# protoboard.net
KiCad netlist of a schematic drawn in EAGLE
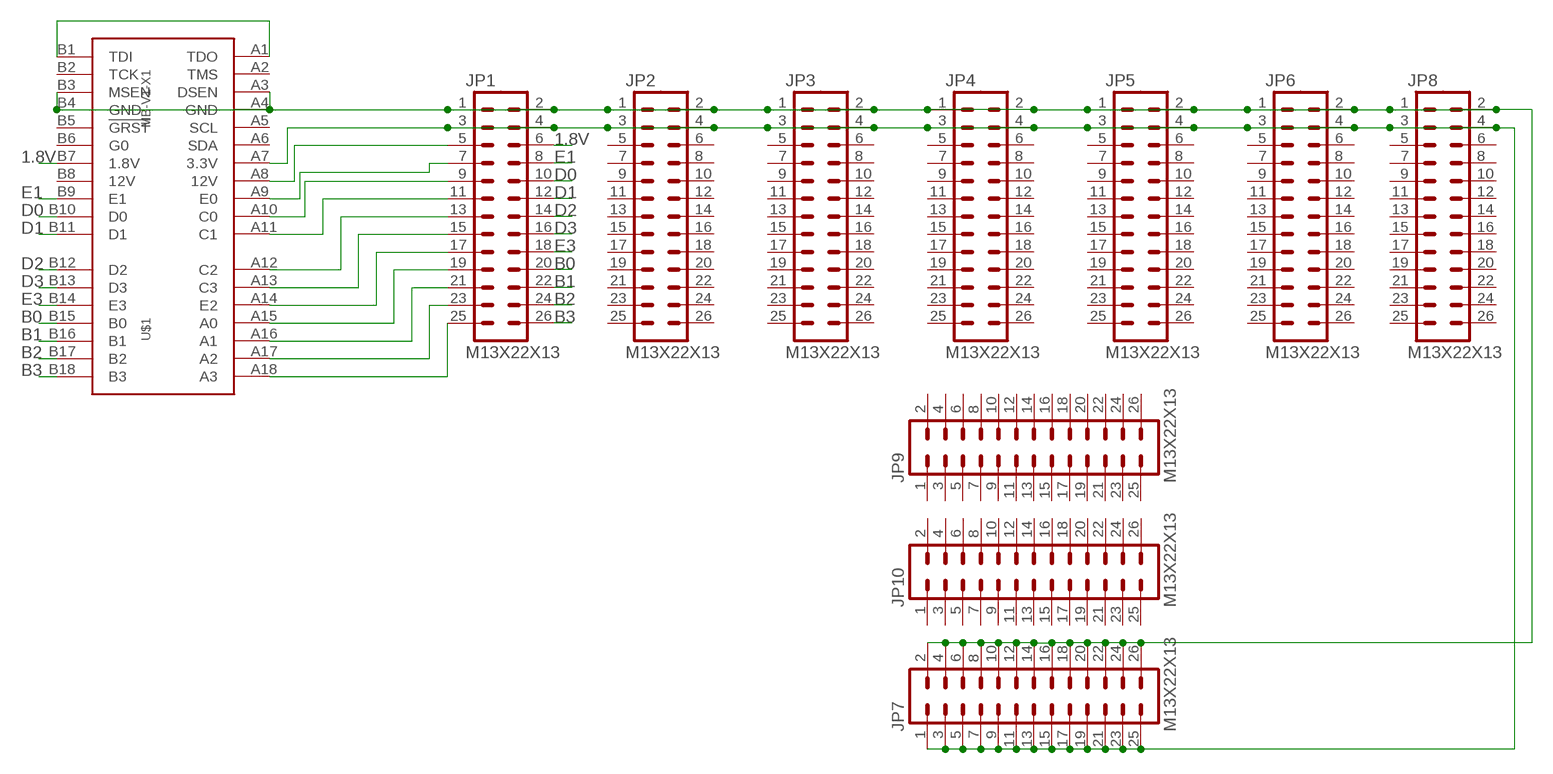
[diagram p0: schematic, sheet 1]

(export (version "E")
  (design (tool "Eeschema 10.0.6"))
  (components
    (comp (ref "JP1")
      (value "M13X22X13")
      (footprint "eagle-import:2X13")
      (libsource (lib "eagle-import") (part "M13X22X13"))
    )
    (comp (ref "JP2")
      (value "M13X22X13")
      (footprint "eagle-import:2X13")
      (libsource (lib "eagle-import") (part "M13X22X13"))
    )
    (comp (ref "JP3")
      (value "M13X22X13")
      (footprint "eagle-import:2X13")
      (libsource (lib "eagle-import") (part "M13X22X13"))
    )
    (comp (ref "JP4")
      (value "M13X22X13")
      (footprint "eagle-import:2X13")
      (libsource (lib "eagle-import") (part "M13X22X13"))
    )
    (comp (ref "JP5")
      (value "M13X22X13")
      (footprint "eagle-import:2X13")
      (libsource (lib "eagle-import") (part "M13X22X13"))
    )
    (comp (ref "JP6")
      (value "M13X22X13")
      (footprint "eagle-import:2X13")
      (libsource (lib "eagle-import") (part "M13X22X13"))
    )
    (comp (ref "JP7")
      (value "M13X22X13")
      (footprint "eagle-import:2X13")
      (libsource (lib "eagle-import") (part "M13X22X13"))
    )
    (comp (ref "JP8")
      (value "M13X22X13")
      (footprint "eagle-import:2X13")
      (libsource (lib "eagle-import") (part "M13X22X13"))
    )
    (comp (ref "JP9")
      (value "M13X22X13")
      (footprint "eagle-import:2X13")
      (libsource (lib "eagle-import") (part "M13X22X13"))
    )
    (comp (ref "JP10")
      (value "M13X22X13")
      (footprint "eagle-import:2X13")
      (libsource (lib "eagle-import") (part "M13X22X13"))
    )
    (comp (ref "U$1")
      (value "MB-V1-X1")
      (footprint "eagle-import:PCIE-X1-EDGE")
      (libsource (lib "eagle-import") (part "MB-V1-X1"))
    )
  )
  (nets
    (net (code "1") (name "/1.8V") (class "Default")
      (node (ref "JP1") (pin "6") (pinfunction "6_6") (pintype "passive"))
      (node (ref "U$1") (pin "B7") (pinfunction "1.8V_B7") (pintype "bidirectional"))
    )
    (net (code "2") (name "/B0") (class "Default")
      (node (ref "JP1") (pin "20") (pinfunction "20_20") (pintype "passive"))
      (node (ref "U$1") (pin "B15") (pinfunction "B0_B15") (pintype "bidirectional"))
    )
    (net (code "3") (name "/B1") (class "Default")
      (node (ref "JP1") (pin "22") (pinfunction "22_22") (pintype "passive"))
      (node (ref "U$1") (pin "B16") (pinfunction "B1_B16") (pintype "bidirectional"))
    )
    (net (code "4") (name "/B2") (class "Default")
      (node (ref "JP1") (pin "24") (pinfunction "24_24") (pintype "passive"))
      (node (ref "U$1") (pin "B17") (pinfunction "B2_B17") (pintype "bidirectional"))
    )
    (net (code "5") (name "/B3") (class "Default")
      (node (ref "JP1") (pin "26") (pinfunction "26_26") (pintype "passive"))
      (node (ref "U$1") (pin "B18") (pinfunction "B3_B18") (pintype "bidirectional"))
    )
    (net (code "6") (name "/D0") (class "Default")
      (node (ref "JP1") (pin "10") (pinfunction "10_10") (pintype "passive"))
      (node (ref "U$1") (pin "B10") (pinfunction "D0_B10") (pintype "bidirectional"))
    )
    (net (code "7") (name "/D1") (class "Default")
      (node (ref "JP1") (pin "12") (pinfunction "12_12") (pintype "passive"))
      (node (ref "U$1") (pin "B11") (pinfunction "D1_B11") (pintype "bidirectional"))
    )
    (net (code "8") (name "/D2") (class "Default")
      (node (ref "JP1") (pin "14") (pinfunction "14_14") (pintype "passive"))
      (node (ref "U$1") (pin "B12") (pinfunction "D2_B12") (pintype "bidirectional"))
    )
    (net (code "9") (name "/D3") (class "Default")
      (node (ref "JP1") (pin "16") (pinfunction "16_16") (pintype "passive"))
      (node (ref "U$1") (pin "B13") (pinfunction "D3_B13") (pintype "bidirectional"))
    )
    (net (code "10") (name "/E1") (class "Default")
      (node (ref "JP1") (pin "8") (pinfunction "8_8") (pintype "passive"))
      (node (ref "U$1") (pin "B9") (pinfunction "E1_B9") (pintype "bidirectional"))
    )
    (net (code "11") (name "/E3") (class "Default")
      (node (ref "JP1") (pin "18") (pinfunction "18_18") (pintype "passive"))
      (node (ref "U$1") (pin "B14") (pinfunction "E3_B14") (pintype "bidirectional"))
    )
    (net (code "12") (name "Net-(JP1-Pad5)") (class "Default")
      (node (ref "JP1") (pin "5") (pinfunction "5_5") (pintype "passive"))
      (node (ref "U$1") (pin "A8") (pinfunction "12V_A8") (pintype "bidirectional"))
    )
    (net (code "13") (name "Net-(U$1-3.3V)") (class "Default")
      (node (ref "JP1") (pin "3") (pinfunction "3_3") (pintype "passive"))
      (node (ref "JP1") (pin "4") (pinfunction "4_4") (pintype "passive"))
      (node (ref "JP2") (pin "3") (pinfunction "3_3") (pintype "passive"))
      (node (ref "JP2") (pin "4") (pinfunction "4_4") (pintype "passive"))
      (node (ref "JP3") (pin "3") (pinfunction "3_3") (pintype "passive"))
      (node (ref "JP3") (pin "4") (pinfunction "4_4") (pintype "passive"))
      (node (ref "JP4") (pin "3") (pinfunction "3_3") (pintype "passive"))
      (node (ref "JP4") (pin "4") (pinfunction "4_4") (pintype "passive"))
      (node (ref "JP5") (pin "3") (pinfunction "3_3") (pintype "passive"))
      (node (ref "JP5") (pin "4") (pinfunction "4_4") (pintype "passive"))
      (node (ref "JP6") (pin "3") (pinfunction "3_3") (pintype "passive"))
      (node (ref "JP6") (pin "4") (pinfunction "4_4") (pintype "passive"))
      (node (ref "JP7") (pin "1") (pinfunction "1_1") (pintype "passive"))
      (node (ref "JP7") (pin "11") (pinfunction "11_11") (pintype "passive"))
      (node (ref "JP7") (pin "13") (pinfunction "13_13") (pintype "passive"))
      (node (ref "JP7") (pin "15") (pinfunction "15_15") (pintype "passive"))
      (node (ref "JP7") (pin "17") (pinfunction "17_17") (pintype "passive"))
      (node (ref "JP7") (pin "19") (pinfunction "19_19") (pintype "passive"))
      (node (ref "JP7") (pin "21") (pinfunction "21_21") (pintype "passive"))
      (node (ref "JP7") (pin "23") (pinfunction "23_23") (pintype "passive"))
      (node (ref "JP7") (pin "25") (pinfunction "25_25") (pintype "passive"))
      (node (ref "JP7") (pin "3") (pinfunction "3_3") (pintype "passive"))
      (node (ref "JP7") (pin "5") (pinfunction "5_5") (pintype "passive"))
      (node (ref "JP7") (pin "7") (pinfunction "7_7") (pintype "passive"))
      (node (ref "JP7") (pin "9") (pinfunction "9_9") (pintype "passive"))
      (node (ref "JP8") (pin "3") (pinfunction "3_3") (pintype "passive"))
      (node (ref "JP8") (pin "4") (pinfunction "4_4") (pintype "passive"))
      (node (ref "U$1") (pin "A7") (pinfunction "3.3V_A7") (pintype "bidirectional"))
    )
    (net (code "14") (name "Net-(U$1-A0)") (class "Default")
      (node (ref "JP1") (pin "19") (pinfunction "19_19") (pintype "passive"))
      (node (ref "U$1") (pin "A15") (pinfunction "A0_A15") (pintype "bidirectional"))
    )
    (net (code "15") (name "Net-(U$1-A1)") (class "Default")
      (node (ref "JP1") (pin "21") (pinfunction "21_21") (pintype "passive"))
      (node (ref "U$1") (pin "A16") (pinfunction "A1_A16") (pintype "bidirectional"))
    )
    (net (code "16") (name "Net-(U$1-A2)") (class "Default")
      (node (ref "JP1") (pin "23") (pinfunction "23_23") (pintype "passive"))
      (node (ref "U$1") (pin "A17") (pinfunction "A2_A17") (pintype "bidirectional"))
    )
    (net (code "17") (name "Net-(U$1-A3)") (class "Default")
      (node (ref "JP1") (pin "25") (pinfunction "25_25") (pintype "passive"))
      (node (ref "U$1") (pin "A18") (pinfunction "A3_A18") (pintype "bidirectional"))
    )
    (net (code "18") (name "Net-(U$1-C0)") (class "Default")
      (node (ref "JP1") (pin "9") (pinfunction "9_9") (pintype "passive"))
      (node (ref "U$1") (pin "A10") (pinfunction "C0_A10") (pintype "bidirectional"))
    )
    (net (code "19") (name "Net-(U$1-C1)") (class "Default")
      (node (ref "JP1") (pin "11") (pinfunction "11_11") (pintype "passive"))
      (node (ref "U$1") (pin "A11") (pinfunction "C1_A11") (pintype "bidirectional"))
    )
    (net (code "20") (name "Net-(U$1-C2)") (class "Default")
      (node (ref "JP1") (pin "13") (pinfunction "13_13") (pintype "passive"))
      (node (ref "U$1") (pin "A12") (pinfunction "C2_A12") (pintype "bidirectional"))
    )
    (net (code "21") (name "Net-(U$1-C3)") (class "Default")
      (node (ref "JP1") (pin "15") (pinfunction "15_15") (pintype "passive"))
      (node (ref "U$1") (pin "A13") (pinfunction "C3_A13") (pintype "bidirectional"))
    )
    (net (code "22") (name "Net-(U$1-DSEN)") (class "Default")
      (node (ref "JP1") (pin "1") (pinfunction "1_1") (pintype "passive"))
      (node (ref "JP1") (pin "2") (pinfunction "2_2") (pintype "passive"))
      (node (ref "JP2") (pin "1") (pinfunction "1_1") (pintype "passive"))
      (node (ref "JP2") (pin "2") (pinfunction "2_2") (pintype "passive"))
      (node (ref "JP3") (pin "1") (pinfunction "1_1") (pintype "passive"))
      (node (ref "JP3") (pin "2") (pinfunction "2_2") (pintype "passive"))
      (node (ref "JP4") (pin "1") (pinfunction "1_1") (pintype "passive"))
      (node (ref "JP4") (pin "2") (pinfunction "2_2") (pintype "passive"))
      (node (ref "JP5") (pin "1") (pinfunction "1_1") (pintype "passive"))
      (node (ref "JP5") (pin "2") (pinfunction "2_2") (pintype "passive"))
      (node (ref "JP6") (pin "1") (pinfunction "1_1") (pintype "passive"))
      (node (ref "JP6") (pin "2") (pinfunction "2_2") (pintype "passive"))
      (node (ref "JP7") (pin "10") (pinfunction "10_10") (pintype "passive"))
      (node (ref "JP7") (pin "12") (pinfunction "12_12") (pintype "passive"))
      (node (ref "JP7") (pin "14") (pinfunction "14_14") (pintype "passive"))
      (node (ref "JP7") (pin "16") (pinfunction "16_16") (pintype "passive"))
      (node (ref "JP7") (pin "18") (pinfunction "18_18") (pintype "passive"))
      (node (ref "JP7") (pin "2") (pinfunction "2_2") (pintype "passive"))
      (node (ref "JP7") (pin "20") (pinfunction "20_20") (pintype "passive"))
      (node (ref "JP7") (pin "22") (pinfunction "22_22") (pintype "passive"))
      (node (ref "JP7") (pin "24") (pinfunction "24_24") (pintype "passive"))
      (node (ref "JP7") (pin "26") (pinfunction "26_26") (pintype "passive"))
      (node (ref "JP7") (pin "4") (pinfunction "4_4") (pintype "passive"))
      (node (ref "JP7") (pin "6") (pinfunction "6_6") (pintype "passive"))
      (node (ref "JP7") (pin "8") (pinfunction "8_8") (pintype "passive"))
      (node (ref "JP8") (pin "1") (pinfunction "1_1") (pintype "passive"))
      (node (ref "JP8") (pin "2") (pinfunction "2_2") (pintype "passive"))
      (node (ref "U$1") (pin "A3") (pinfunction "DSEN_A3") (pintype "bidirectional"))
      (node (ref "U$1") (pin "A4") (pinfunction "GND_A4") (pintype "bidirectional"))
      (node (ref "U$1") (pin "B3") (pinfunction "MSEN_B3") (pintype "bidirectional"))
      (node (ref "U$1") (pin "B4") (pinfunction "GND_B4") (pintype "bidirectional"))
    )
    (net (code "23") (name "Net-(U$1-E0)") (class "Default")
      (node (ref "JP1") (pin "7") (pinfunction "7_7") (pintype "passive"))
      (node (ref "U$1") (pin "A9") (pinfunction "E0_A9") (pintype "bidirectional"))
    )
    (net (code "24") (name "Net-(U$1-E2)") (class "Default")
      (node (ref "JP1") (pin "17") (pinfunction "17_17") (pintype "passive"))
      (node (ref "U$1") (pin "A14") (pinfunction "E2_A14") (pintype "bidirectional"))
    )
    (net (code "25") (name "Net-(U$1-TDI)") (class "Default")
      (node (ref "U$1") (pin "A1") (pinfunction "TDO_A1") (pintype "bidirectional"))
      (node (ref "U$1") (pin "B1") (pinfunction "TDI_B1") (pintype "bidirectional"))
    )
    (net (code "26") (name "unconnected-(JP2-Pad5)") (class "Default")
      (node (ref "JP2") (pin "5") (pinfunction "5_5") (pintype "passive"))
    )
    (net (code "27") (name "unconnected-(JP2-Pad6)") (class "Default")
      (node (ref "JP2") (pin "6") (pinfunction "6_6") (pintype "passive"))
    )
    (net (code "28") (name "unconnected-(JP2-Pad7)") (class "Default")
      (node (ref "JP2") (pin "7") (pinfunction "7_7") (pintype "passive"))
    )
    (net (code "29") (name "unconnected-(JP2-Pad8)") (class "Default")
      (node (ref "JP2") (pin "8") (pinfunction "8_8") (pintype "passive"))
    )
    (net (code "30") (name "unconnected-(JP2-Pad9)") (class "Default")
      (node (ref "JP2") (pin "9") (pinfunction "9_9") (pintype "passive"))
    )
    (net (code "31") (name "unconnected-(JP2-Pad10)") (class "Default")
      (node (ref "JP2") (pin "10") (pinfunction "10_10") (pintype "passive"))
    )
    (net (code "32") (name "unconnected-(JP2-Pad11)") (class "Default")
      (node (ref "JP2") (pin "11") (pinfunction "11_11") (pintype "passive"))
    )
    (net (code "33") (name "unconnected-(JP2-Pad12)") (class "Default")
      (node (ref "JP2") (pin "12") (pinfunction "12_12") (pintype "passive"))
    )
    (net (code "34") (name "unconnected-(JP2-Pad13)") (class "Default")
      (node (ref "JP2") (pin "13") (pinfunction "13_13") (pintype "passive"))
    )
    (net (code "35") (name "unconnected-(JP2-Pad14)") (class "Default")
      (node (ref "JP2") (pin "14") (pinfunction "14_14") (pintype "passive"))
    )
    (net (code "36") (name "unconnected-(JP2-Pad15)") (class "Default")
      (node (ref "JP2") (pin "15") (pinfunction "15_15") (pintype "passive"))
    )
    (net (code "37") (name "unconnected-(JP2-Pad16)") (class "Default")
      (node (ref "JP2") (pin "16") (pinfunction "16_16") (pintype "passive"))
    )
    (net (code "38") (name "unconnected-(JP2-Pad17)") (class "Default")
      (node (ref "JP2") (pin "17") (pinfunction "17_17") (pintype "passive"))
    )
    (net (code "39") (name "unconnected-(JP2-Pad18)") (class "Default")
      (node (ref "JP2") (pin "18") (pinfunction "18_18") (pintype "passive"))
    )
    (net (code "40") (name "unconnected-(JP2-Pad19)") (class "Default")
      (node (ref "JP2") (pin "19") (pinfunction "19_19") (pintype "passive"))
    )
    (net (code "41") (name "unconnected-(JP2-Pad20)") (class "Default")
      (node (ref "JP2") (pin "20") (pinfunction "20_20") (pintype "passive"))
    )
    (net (code "42") (name "unconnected-(JP2-Pad21)") (class "Default")
      (node (ref "JP2") (pin "21") (pinfunction "21_21") (pintype "passive"))
    )
    (net (code "43") (name "unconnected-(JP2-Pad22)") (class "Default")
      (node (ref "JP2") (pin "22") (pinfunction "22_22") (pintype "passive"))
    )
    (net (code "44") (name "unconnected-(JP2-Pad23)") (class "Default")
      (node (ref "JP2") (pin "23") (pinfunction "23_23") (pintype "passive"))
    )
    (net (code "45") (name "unconnected-(JP2-Pad24)") (class "Default")
      (node (ref "JP2") (pin "24") (pinfunction "24_24") (pintype "passive"))
    )
    (net (code "46") (name "unconnected-(JP2-Pad25)") (class "Default")
      (node (ref "JP2") (pin "25") (pinfunction "25_25") (pintype "passive"))
    )
    (net (code "47") (name "unconnected-(JP2-Pad26)") (class "Default")
      (node (ref "JP2") (pin "26") (pinfunction "26_26") (pintype "passive"))
    )
    (net (code "48") (name "unconnected-(JP3-Pad5)") (class "Default")
      (node (ref "JP3") (pin "5") (pinfunction "5_5") (pintype "passive"))
    )
    (net (code "49") (name "unconnected-(JP3-Pad6)") (class "Default")
      (node (ref "JP3") (pin "6") (pinfunction "6_6") (pintype "passive"))
    )
    (net (code "50") (name "unconnected-(JP3-Pad7)") (class "Default")
      (node (ref "JP3") (pin "7") (pinfunction "7_7") (pintype "passive"))
    )
    (net (code "51") (name "unconnected-(JP3-Pad8)") (class "Default")
      (node (ref "JP3") (pin "8") (pinfunction "8_8") (pintype "passive"))
    )
    (net (code "52") (name "unconnected-(JP3-Pad9)") (class "Default")
      (node (ref "JP3") (pin "9") (pinfunction "9_9") (pintype "passive"))
    )
    (net (code "53") (name "unconnected-(JP3-Pad10)") (class "Default")
      (node (ref "JP3") (pin "10") (pinfunction "10_10") (pintype "passive"))
    )
    (net (code "54") (name "unconnected-(JP3-Pad11)") (class "Default")
      (node (ref "JP3") (pin "11") (pinfunction "11_11") (pintype "passive"))
    )
    (net (code "55") (name "unconnected-(JP3-Pad12)") (class "Default")
      (node (ref "JP3") (pin "12") (pinfunction "12_12") (pintype "passive"))
    )
    (net (code "56") (name "unconnected-(JP3-Pad13)") (class "Default")
      (node (ref "JP3") (pin "13") (pinfunction "13_13") (pintype "passive"))
    )
    (net (code "57") (name "unconnected-(JP3-Pad14)") (class "Default")
      (node (ref "JP3") (pin "14") (pinfunction "14_14") (pintype "passive"))
    )
    (net (code "58") (name "unconnected-(JP3-Pad15)") (class "Default")
      (node (ref "JP3") (pin "15") (pinfunction "15_15") (pintype "passive"))
    )
    (net (code "59") (name "unconnected-(JP3-Pad16)") (class "Default")
      (node (ref "JP3") (pin "16") (pinfunction "16_16") (pintype "passive"))
    )
    (net (code "60") (name "unconnected-(JP3-Pad17)") (class "Default")
      (node (ref "JP3") (pin "17") (pinfunction "17_17") (pintype "passive"))
    )
    (net (code "61") (name "unconnected-(JP3-Pad18)") (class "Default")
      (node (ref "JP3") (pin "18") (pinfunction "18_18") (pintype "passive"))
    )
    (net (code "62") (name "unconnected-(JP3-Pad19)") (class "Default")
      (node (ref "JP3") (pin "19") (pinfunction "19_19") (pintype "passive"))
    )
    (net (code "63") (name "unconnected-(JP3-Pad20)") (class "Default")
      (node (ref "JP3") (pin "20") (pinfunction "20_20") (pintype "passive"))
    )
    (net (code "64") (name "unconnected-(JP3-Pad21)") (class "Default")
      (node (ref "JP3") (pin "21") (pinfunction "21_21") (pintype "passive"))
    )
    (net (code "65") (name "unconnected-(JP3-Pad22)") (class "Default")
      (node (ref "JP3") (pin "22") (pinfunction "22_22") (pintype "passive"))
    )
    (net (code "66") (name "unconnected-(JP3-Pad23)") (class "Default")
      (node (ref "JP3") (pin "23") (pinfunction "23_23") (pintype "passive"))
    )
    (net (code "67") (name "unconnected-(JP3-Pad24)") (class "Default")
      (node (ref "JP3") (pin "24") (pinfunction "24_24") (pintype "passive"))
    )
    (net (code "68") (name "unconnected-(JP3-Pad25)") (class "Default")
      (node (ref "JP3") (pin "25") (pinfunction "25_25") (pintype "passive"))
    )
    (net (code "69") (name "unconnected-(JP3-Pad26)") (class "Default")
      (node (ref "JP3") (pin "26") (pinfunction "26_26") (pintype "passive"))
    )
    (net (code "70") (name "unconnected-(JP4-Pad5)") (class "Default")
      (node (ref "JP4") (pin "5") (pinfunction "5_5") (pintype "passive"))
    )
    (net (code "71") (name "unconnected-(JP4-Pad6)") (class "Default")
      (node (ref "JP4") (pin "6") (pinfunction "6_6") (pintype "passive"))
    )
    (net (code "72") (name "unconnected-(JP4-Pad7)") (class "Default")
      (node (ref "JP4") (pin "7") (pinfunction "7_7") (pintype "passive"))
    )
    (net (code "73") (name "unconnected-(JP4-Pad8)") (class "Default")
      (node (ref "JP4") (pin "8") (pinfunction "8_8") (pintype "passive"))
    )
    (net (code "74") (name "unconnected-(JP4-Pad9)") (class "Default")
      (node (ref "JP4") (pin "9") (pinfunction "9_9") (pintype "passive"))
    )
    (net (code "75") (name "unconnected-(JP4-Pad10)") (class "Default")
      (node (ref "JP4") (pin "10") (pinfunction "10_10") (pintype "passive"))
    )
    (net (code "76") (name "unconnected-(JP4-Pad11)") (class "Default")
      (node (ref "JP4") (pin "11") (pinfunction "11_11") (pintype "passive"))
    )
    (net (code "77") (name "unconnected-(JP4-Pad12)") (class "Default")
      (node (ref "JP4") (pin "12") (pinfunction "12_12") (pintype "passive"))
    )
    (net (code "78") (name "unconnected-(JP4-Pad13)") (class "Default")
      (node (ref "JP4") (pin "13") (pinfunction "13_13") (pintype "passive"))
    )
    (net (code "79") (name "unconnected-(JP4-Pad14)") (class "Default")
      (node (ref "JP4") (pin "14") (pinfunction "14_14") (pintype "passive"))
    )
    (net (code "80") (name "unconnected-(JP4-Pad15)") (class "Default")
      (node (ref "JP4") (pin "15") (pinfunction "15_15") (pintype "passive"))
    )
    (net (code "81") (name "unconnected-(JP4-Pad16)") (class "Default")
      (node (ref "JP4") (pin "16") (pinfunction "16_16") (pintype "passive"))
    )
    (net (code "82") (name "unconnected-(JP4-Pad17)") (class "Default")
      (node (ref "JP4") (pin "17") (pinfunction "17_17") (pintype "passive"))
    )
    (net (code "83") (name "unconnected-(JP4-Pad18)") (class "Default")
      (node (ref "JP4") (pin "18") (pinfunction "18_18") (pintype "passive"))
    )
    (net (code "84") (name "unconnected-(JP4-Pad19)") (class "Default")
      (node (ref "JP4") (pin "19") (pinfunction "19_19") (pintype "passive"))
    )
    (net (code "85") (name "unconnected-(JP4-Pad20)") (class "Default")
      (node (ref "JP4") (pin "20") (pinfunction "20_20") (pintype "passive"))
    )
    (net (code "86") (name "unconnected-(JP4-Pad21)") (class "Default")
      (node (ref "JP4") (pin "21") (pinfunction "21_21") (pintype "passive"))
    )
    (net (code "87") (name "unconnected-(JP4-Pad22)") (class "Default")
      (node (ref "JP4") (pin "22") (pinfunction "22_22") (pintype "passive"))
    )
    (net (code "88") (name "unconnected-(JP4-Pad23)") (class "Default")
      (node (ref "JP4") (pin "23") (pinfunction "23_23") (pintype "passive"))
    )
    (net (code "89") (name "unconnected-(JP4-Pad24)") (class "Default")
      (node (ref "JP4") (pin "24") (pinfunction "24_24") (pintype "passive"))
    )
    (net (code "90") (name "unconnected-(JP4-Pad25)") (class "Default")
      (node (ref "JP4") (pin "25") (pinfunction "25_25") (pintype "passive"))
    )
    (net (code "91") (name "unconnected-(JP4-Pad26)") (class "Default")
      (node (ref "JP4") (pin "26") (pinfunction "26_26") (pintype "passive"))
    )
    (net (code "92") (name "unconnected-(JP5-Pad5)") (class "Default")
      (node (ref "JP5") (pin "5") (pinfunction "5_5") (pintype "passive"))
    )
    (net (code "93") (name "unconnected-(JP5-Pad6)") (class "Default")
      (node (ref "JP5") (pin "6") (pinfunction "6_6") (pintype "passive"))
    )
    (net (code "94") (name "unconnected-(JP5-Pad7)") (class "Default")
      (node (ref "JP5") (pin "7") (pinfunction "7_7") (pintype "passive"))
    )
    (net (code "95") (name "unconnected-(JP5-Pad8)") (class "Default")
      (node (ref "JP5") (pin "8") (pinfunction "8_8") (pintype "passive"))
    )
    (net (code "96") (name "unconnected-(JP5-Pad9)") (class "Default")
      (node (ref "JP5") (pin "9") (pinfunction "9_9") (pintype "passive"))
    )
    (net (code "97") (name "unconnected-(JP5-Pad10)") (class "Default")
      (node (ref "JP5") (pin "10") (pinfunction "10_10") (pintype "passive"))
    )
    (net (code "98") (name "unconnected-(JP5-Pad11)") (class "Default")
      (node (ref "JP5") (pin "11") (pinfunction "11_11") (pintype "passive"))
    )
    (net (code "99") (name "unconnected-(JP5-Pad12)") (class "Default")
      (node (ref "JP5") (pin "12") (pinfunction "12_12") (pintype "passive"))
    )
    (net (code "100") (name "unconnected-(JP5-Pad13)") (class "Default")
      (node (ref "JP5") (pin "13") (pinfunction "13_13") (pintype "passive"))
    )
    (net (code "101") (name "unconnected-(JP5-Pad14)") (class "Default")
      (node (ref "JP5") (pin "14") (pinfunction "14_14") (pintype "passive"))
    )
    (net (code "102") (name "unconnected-(JP5-Pad15)") (class "Default")
      (node (ref "JP5") (pin "15") (pinfunction "15_15") (pintype "passive"))
    )
    (net (code "103") (name "unconnected-(JP5-Pad16)") (class "Default")
      (node (ref "JP5") (pin "16") (pinfunction "16_16") (pintype "passive"))
    )
    (net (code "104") (name "unconnected-(JP5-Pad17)") (class "Default")
      (node (ref "JP5") (pin "17") (pinfunction "17_17") (pintype "passive"))
    )
    (net (code "105") (name "unconnected-(JP5-Pad18)") (class "Default")
      (node (ref "JP5") (pin "18") (pinfunction "18_18") (pintype "passive"))
    )
    (net (code "106") (name "unconnected-(JP5-Pad19)") (class "Default")
      (node (ref "JP5") (pin "19") (pinfunction "19_19") (pintype "passive"))
    )
    (net (code "107") (name "unconnected-(JP5-Pad20)") (class "Default")
      (node (ref "JP5") (pin "20") (pinfunction "20_20") (pintype "passive"))
    )
    (net (code "108") (name "unconnected-(JP5-Pad21)") (class "Default")
      (node (ref "JP5") (pin "21") (pinfunction "21_21") (pintype "passive"))
    )
    (net (code "109") (name "unconnected-(JP5-Pad22)") (class "Default")
      (node (ref "JP5") (pin "22") (pinfunction "22_22") (pintype "passive"))
    )
    (net (code "110") (name "unconnected-(JP5-Pad23)") (class "Default")
      (node (ref "JP5") (pin "23") (pinfunction "23_23") (pintype "passive"))
    )
    (net (code "111") (name "unconnected-(JP5-Pad24)") (class "Default")
      (node (ref "JP5") (pin "24") (pinfunction "24_24") (pintype "passive"))
    )
    (net (code "112") (name "unconnected-(JP5-Pad25)") (class "Default")
      (node (ref "JP5") (pin "25") (pinfunction "25_25") (pintype "passive"))
    )
    (net (code "113") (name "unconnected-(JP5-Pad26)") (class "Default")
      (node (ref "JP5") (pin "26") (pinfunction "26_26") (pintype "passive"))
    )
    (net (code "114") (name "unconnected-(JP6-Pad5)") (class "Default")
      (node (ref "JP6") (pin "5") (pinfunction "5_5") (pintype "passive"))
    )
    (net (code "115") (name "unconnected-(JP6-Pad6)") (class "Default")
      (node (ref "JP6") (pin "6") (pinfunction "6_6") (pintype "passive"))
    )
    (net (code "116") (name "unconnected-(JP6-Pad7)") (class "Default")
      (node (ref "JP6") (pin "7") (pinfunction "7_7") (pintype "passive"))
    )
    (net (code "117") (name "unconnected-(JP6-Pad8)") (class "Default")
      (node (ref "JP6") (pin "8") (pinfunction "8_8") (pintype "passive"))
    )
    (net (code "118") (name "unconnected-(JP6-Pad9)") (class "Default")
      (node (ref "JP6") (pin "9") (pinfunction "9_9") (pintype "passive"))
    )
    (net (code "119") (name "unconnected-(JP6-Pad10)") (class "Default")
      (node (ref "JP6") (pin "10") (pinfunction "10_10") (pintype "passive"))
    )
    (net (code "120") (name "unconnected-(JP6-Pad11)") (class "Default")
      (node (ref "JP6") (pin "11") (pinfunction "11_11") (pintype "passive"))
    )
    (net (code "121") (name "unconnected-(JP6-Pad12)") (class "Default")
      (node (ref "JP6") (pin "12") (pinfunction "12_12") (pintype "passive"))
    )
    (net (code "122") (name "unconnected-(JP6-Pad13)") (class "Default")
      (node (ref "JP6") (pin "13") (pinfunction "13_13") (pintype "passive"))
    )
    (net (code "123") (name "unconnected-(JP6-Pad14)") (class "Default")
      (node (ref "JP6") (pin "14") (pinfunction "14_14") (pintype "passive"))
    )
    (net (code "124") (name "unconnected-(JP6-Pad15)") (class "Default")
      (node (ref "JP6") (pin "15") (pinfunction "15_15") (pintype "passive"))
    )
    (net (code "125") (name "unconnected-(JP6-Pad16)") (class "Default")
      (node (ref "JP6") (pin "16") (pinfunction "16_16") (pintype "passive"))
    )
    (net (code "126") (name "unconnected-(JP6-Pad17)") (class "Default")
      (node (ref "JP6") (pin "17") (pinfunction "17_17") (pintype "passive"))
    )
    (net (code "127") (name "unconnected-(JP6-Pad18)") (class "Default")
      (node (ref "JP6") (pin "18") (pinfunction "18_18") (pintype "passive"))
    )
    (net (code "128") (name "unconnected-(JP6-Pad19)") (class "Default")
      (node (ref "JP6") (pin "19") (pinfunction "19_19") (pintype "passive"))
    )
    (net (code "129") (name "unconnected-(JP6-Pad20)") (class "Default")
      (node (ref "JP6") (pin "20") (pinfunction "20_20") (pintype "passive"))
    )
    (net (code "130") (name "unconnected-(JP6-Pad21)") (class "Default")
      (node (ref "JP6") (pin "21") (pinfunction "21_21") (pintype "passive"))
    )
    (net (code "131") (name "unconnected-(JP6-Pad22)") (class "Default")
      (node (ref "JP6") (pin "22") (pinfunction "22_22") (pintype "passive"))
    )
    (net (code "132") (name "unconnected-(JP6-Pad23)") (class "Default")
      (node (ref "JP6") (pin "23") (pinfunction "23_23") (pintype "passive"))
    )
    (net (code "133") (name "unconnected-(JP6-Pad24)") (class "Default")
      (node (ref "JP6") (pin "24") (pinfunction "24_24") (pintype "passive"))
    )
    (net (code "134") (name "unconnected-(JP6-Pad25)") (class "Default")
      (node (ref "JP6") (pin "25") (pinfunction "25_25") (pintype "passive"))
    )
    (net (code "135") (name "unconnected-(JP6-Pad26)") (class "Default")
      (node (ref "JP6") (pin "26") (pinfunction "26_26") (pintype "passive"))
    )
    (net (code "136") (name "unconnected-(JP8-Pad5)") (class "Default")
      (node (ref "JP8") (pin "5") (pinfunction "5_5") (pintype "passive"))
    )
    (net (code "137") (name "unconnected-(JP8-Pad6)") (class "Default")
      (node (ref "JP8") (pin "6") (pinfunction "6_6") (pintype "passive"))
    )
    (net (code "138") (name "unconnected-(JP8-Pad7)") (class "Default")
      (node (ref "JP8") (pin "7") (pinfunction "7_7") (pintype "passive"))
    )
    (net (code "139") (name "unconnected-(JP8-Pad8)") (class "Default")
      (node (ref "JP8") (pin "8") (pinfunction "8_8") (pintype "passive"))
    )
    (net (code "140") (name "unconnected-(JP8-Pad9)") (class "Default")
      (node (ref "JP8") (pin "9") (pinfunction "9_9") (pintype "passive"))
    )
    (net (code "141") (name "unconnected-(JP8-Pad10)") (class "Default")
      (node (ref "JP8") (pin "10") (pinfunction "10_10") (pintype "passive"))
    )
    (net (code "142") (name "unconnected-(JP8-Pad11)") (class "Default")
      (node (ref "JP8") (pin "11") (pinfunction "11_11") (pintype "passive"))
    )
    (net (code "143") (name "unconnected-(JP8-Pad12)") (class "Default")
      (node (ref "JP8") (pin "12") (pinfunction "12_12") (pintype "passive"))
    )
    (net (code "144") (name "unconnected-(JP8-Pad13)") (class "Default")
      (node (ref "JP8") (pin "13") (pinfunction "13_13") (pintype "passive"))
    )
    (net (code "145") (name "unconnected-(JP8-Pad14)") (class "Default")
      (node (ref "JP8") (pin "14") (pinfunction "14_14") (pintype "passive"))
    )
    (net (code "146") (name "unconnected-(JP8-Pad15)") (class "Default")
      (node (ref "JP8") (pin "15") (pinfunction "15_15") (pintype "passive"))
    )
    (net (code "147") (name "unconnected-(JP8-Pad16)") (class "Default")
      (node (ref "JP8") (pin "16") (pinfunction "16_16") (pintype "passive"))
    )
    (net (code "148") (name "unconnected-(JP8-Pad17)") (class "Default")
      (node (ref "JP8") (pin "17") (pinfunction "17_17") (pintype "passive"))
    )
    (net (code "149") (name "unconnected-(JP8-Pad18)") (class "Default")
      (node (ref "JP8") (pin "18") (pinfunction "18_18") (pintype "passive"))
    )
    (net (code "150") (name "unconnected-(JP8-Pad19)") (class "Default")
      (node (ref "JP8") (pin "19") (pinfunction "19_19") (pintype "passive"))
    )
    (net (code "151") (name "unconnected-(JP8-Pad20)") (class "Default")
      (node (ref "JP8") (pin "20") (pinfunction "20_20") (pintype "passive"))
    )
    (net (code "152") (name "unconnected-(JP8-Pad21)") (class "Default")
      (node (ref "JP8") (pin "21") (pinfunction "21_21") (pintype "passive"))
    )
    (net (code "153") (name "unconnected-(JP8-Pad22)") (class "Default")
      (node (ref "JP8") (pin "22") (pinfunction "22_22") (pintype "passive"))
    )
    (net (code "154") (name "unconnected-(JP8-Pad23)") (class "Default")
      (node (ref "JP8") (pin "23") (pinfunction "23_23") (pintype "passive"))
    )
    (net (code "155") (name "unconnected-(JP8-Pad24)") (class "Default")
      (node (ref "JP8") (pin "24") (pinfunction "24_24") (pintype "passive"))
    )
    (net (code "156") (name "unconnected-(JP8-Pad25)") (class "Default")
      (node (ref "JP8") (pin "25") (pinfunction "25_25") (pintype "passive"))
    )
    (net (code "157") (name "unconnected-(JP8-Pad26)") (class "Default")
      (node (ref "JP8") (pin "26") (pinfunction "26_26") (pintype "passive"))
    )
    (net (code "158") (name "unconnected-(JP9-Pad1)") (class "Default")
      (node (ref "JP9") (pin "1") (pinfunction "1_1") (pintype "passive"))
    )
    (net (code "159") (name "unconnected-(JP9-Pad2)") (class "Default")
      (node (ref "JP9") (pin "2") (pinfunction "2_2") (pintype "passive"))
    )
    (net (code "160") (name "unconnected-(JP9-Pad3)") (class "Default")
      (node (ref "JP9") (pin "3") (pinfunction "3_3") (pintype "passive"))
    )
    (net (code "161") (name "unconnected-(JP9-Pad4)") (class "Default")
      (node (ref "JP9") (pin "4") (pinfunction "4_4") (pintype "passive"))
    )
    (net (code "162") (name "unconnected-(JP9-Pad5)") (class "Default")
      (node (ref "JP9") (pin "5") (pinfunction "5_5") (pintype "passive"))
    )
    (net (code "163") (name "unconnected-(JP9-Pad6)") (class "Default")
      (node (ref "JP9") (pin "6") (pinfunction "6_6") (pintype "passive"))
    )
    (net (code "164") (name "unconnected-(JP9-Pad7)") (class "Default")
      (node (ref "JP9") (pin "7") (pinfunction "7_7") (pintype "passive"))
    )
    (net (code "165") (name "unconnected-(JP9-Pad8)") (class "Default")
      (node (ref "JP9") (pin "8") (pinfunction "8_8") (pintype "passive"))
    )
    (net (code "166") (name "unconnected-(JP9-Pad9)") (class "Default")
      (node (ref "JP9") (pin "9") (pinfunction "9_9") (pintype "passive"))
    )
    (net (code "167") (name "unconnected-(JP9-Pad10)") (class "Default")
      (node (ref "JP9") (pin "10") (pinfunction "10_10") (pintype "passive"))
    )
    (net (code "168") (name "unconnected-(JP9-Pad11)") (class "Default")
      (node (ref "JP9") (pin "11") (pinfunction "11_11") (pintype "passive"))
    )
    (net (code "169") (name "unconnected-(JP9-Pad12)") (class "Default")
      (node (ref "JP9") (pin "12") (pinfunction "12_12") (pintype "passive"))
    )
    (net (code "170") (name "unconnected-(JP9-Pad13)") (class "Default")
      (node (ref "JP9") (pin "13") (pinfunction "13_13") (pintype "passive"))
    )
    (net (code "171") (name "unconnected-(JP9-Pad14)") (class "Default")
      (node (ref "JP9") (pin "14") (pinfunction "14_14") (pintype "passive"))
    )
    (net (code "172") (name "unconnected-(JP9-Pad15)") (class "Default")
      (node (ref "JP9") (pin "15") (pinfunction "15_15") (pintype "passive"))
    )
    (net (code "173") (name "unconnected-(JP9-Pad16)") (class "Default")
      (node (ref "JP9") (pin "16") (pinfunction "16_16") (pintype "passive"))
    )
    (net (code "174") (name "unconnected-(JP9-Pad17)") (class "Default")
      (node (ref "JP9") (pin "17") (pinfunction "17_17") (pintype "passive"))
    )
    (net (code "175") (name "unconnected-(JP9-Pad18)") (class "Default")
      (node (ref "JP9") (pin "18") (pinfunction "18_18") (pintype "passive"))
    )
    (net (code "176") (name "unconnected-(JP9-Pad19)") (class "Default")
      (node (ref "JP9") (pin "19") (pinfunction "19_19") (pintype "passive"))
    )
    (net (code "177") (name "unconnected-(JP9-Pad20)") (class "Default")
      (node (ref "JP9") (pin "20") (pinfunction "20_20") (pintype "passive"))
    )
    (net (code "178") (name "unconnected-(JP9-Pad21)") (class "Default")
      (node (ref "JP9") (pin "21") (pinfunction "21_21") (pintype "passive"))
    )
    (net (code "179") (name "unconnected-(JP9-Pad22)") (class "Default")
      (node (ref "JP9") (pin "22") (pinfunction "22_22") (pintype "passive"))
    )
    (net (code "180") (name "unconnected-(JP9-Pad23)") (class "Default")
      (node (ref "JP9") (pin "23") (pinfunction "23_23") (pintype "passive"))
    )
    (net (code "181") (name "unconnected-(JP9-Pad24)") (class "Default")
      (node (ref "JP9") (pin "24") (pinfunction "24_24") (pintype "passive"))
    )
    (net (code "182") (name "unconnected-(JP9-Pad25)") (class "Default")
      (node (ref "JP9") (pin "25") (pinfunction "25_25") (pintype "passive"))
    )
    (net (code "183") (name "unconnected-(JP9-Pad26)") (class "Default")
      (node (ref "JP9") (pin "26") (pinfunction "26_26") (pintype "passive"))
    )
    (net (code "184") (name "unconnected-(JP10-Pad1)") (class "Default")
      (node (ref "JP10") (pin "1") (pinfunction "1_1") (pintype "passive"))
    )
    (net (code "185") (name "unconnected-(JP10-Pad2)") (class "Default")
      (node (ref "JP10") (pin "2") (pinfunction "2_2") (pintype "passive"))
    )
    (net (code "186") (name "unconnected-(JP10-Pad3)") (class "Default")
      (node (ref "JP10") (pin "3") (pinfunction "3_3") (pintype "passive"))
    )
    (net (code "187") (name "unconnected-(JP10-Pad4)") (class "Default")
      (node (ref "JP10") (pin "4") (pinfunction "4_4") (pintype "passive"))
    )
    (net (code "188") (name "unconnected-(JP10-Pad5)") (class "Default")
      (node (ref "JP10") (pin "5") (pinfunction "5_5") (pintype "passive"))
    )
    (net (code "189") (name "unconnected-(JP10-Pad6)") (class "Default")
      (node (ref "JP10") (pin "6") (pinfunction "6_6") (pintype "passive"))
    )
    (net (code "190") (name "unconnected-(JP10-Pad7)") (class "Default")
      (node (ref "JP10") (pin "7") (pinfunction "7_7") (pintype "passive"))
    )
    (net (code "191") (name "unconnected-(JP10-Pad8)") (class "Default")
      (node (ref "JP10") (pin "8") (pinfunction "8_8") (pintype "passive"))
    )
    (net (code "192") (name "unconnected-(JP10-Pad9)") (class "Default")
      (node (ref "JP10") (pin "9") (pinfunction "9_9") (pintype "passive"))
    )
    (net (code "193") (name "unconnected-(JP10-Pad10)") (class "Default")
      (node (ref "JP10") (pin "10") (pinfunction "10_10") (pintype "passive"))
    )
    (net (code "194") (name "unconnected-(JP10-Pad11)") (class "Default")
      (node (ref "JP10") (pin "11") (pinfunction "11_11") (pintype "passive"))
    )
    (net (code "195") (name "unconnected-(JP10-Pad12)") (class "Default")
      (node (ref "JP10") (pin "12") (pinfunction "12_12") (pintype "passive"))
    )
    (net (code "196") (name "unconnected-(JP10-Pad13)") (class "Default")
      (node (ref "JP10") (pin "13") (pinfunction "13_13") (pintype "passive"))
    )
    (net (code "197") (name "unconnected-(JP10-Pad14)") (class "Default")
      (node (ref "JP10") (pin "14") (pinfunction "14_14") (pintype "passive"))
    )
    (net (code "198") (name "unconnected-(JP10-Pad15)") (class "Default")
      (node (ref "JP10") (pin "15") (pinfunction "15_15") (pintype "passive"))
    )
    (net (code "199") (name "unconnected-(JP10-Pad16)") (class "Default")
      (node (ref "JP10") (pin "16") (pinfunction "16_16") (pintype "passive"))
    )
    (net (code "200") (name "unconnected-(JP10-Pad17)") (class "Default")
      (node (ref "JP10") (pin "17") (pinfunction "17_17") (pintype "passive"))
    )
    (net (code "201") (name "unconnected-(JP10-Pad18)") (class "Default")
      (node (ref "JP10") (pin "18") (pinfunction "18_18") (pintype "passive"))
    )
    (net (code "202") (name "unconnected-(JP10-Pad19)") (class "Default")
      (node (ref "JP10") (pin "19") (pinfunction "19_19") (pintype "passive"))
    )
    (net (code "203") (name "unconnected-(JP10-Pad20)") (class "Default")
      (node (ref "JP10") (pin "20") (pinfunction "20_20") (pintype "passive"))
    )
    (net (code "204") (name "unconnected-(JP10-Pad21)") (class "Default")
      (node (ref "JP10") (pin "21") (pinfunction "21_21") (pintype "passive"))
    )
    (net (code "205") (name "unconnected-(JP10-Pad22)") (class "Default")
      (node (ref "JP10") (pin "22") (pinfunction "22_22") (pintype "passive"))
    )
    (net (code "206") (name "unconnected-(JP10-Pad23)") (class "Default")
      (node (ref "JP10") (pin "23") (pinfunction "23_23") (pintype "passive"))
    )
    (net (code "207") (name "unconnected-(JP10-Pad24)") (class "Default")
      (node (ref "JP10") (pin "24") (pinfunction "24_24") (pintype "passive"))
    )
    (net (code "208") (name "unconnected-(JP10-Pad25)") (class "Default")
      (node (ref "JP10") (pin "25") (pinfunction "25_25") (pintype "passive"))
    )
    (net (code "209") (name "unconnected-(JP10-Pad26)") (class "Default")
      (node (ref "JP10") (pin "26") (pinfunction "26_26") (pintype "passive"))
    )
    (net (code "210") (name "unconnected-(U$1-12V-PadB8)") (class "Default")
      (node (ref "U$1") (pin "B8") (pinfunction "12V_B8") (pintype "bidirectional"))
    )
    (net (code "211") (name "unconnected-(U$1-G0-PadB6)") (class "Default")
      (node (ref "U$1") (pin "B6") (pinfunction "G0_B6") (pintype "bidirectional"))
    )
    (net (code "212") (name "unconnected-(U$1-SCL-PadA5)") (class "Default")
      (node (ref "U$1") (pin "A5") (pinfunction "SCL_A5") (pintype "bidirectional"))
    )
    (net (code "213") (name "unconnected-(U$1-SDA-PadA6)") (class "Default")
      (node (ref "U$1") (pin "A6") (pinfunction "SDA_A6") (pintype "bidirectional"))
    )
    (net (code "214") (name "unconnected-(U$1-TCK-PadB2)") (class "Default")
      (node (ref "U$1") (pin "B2") (pinfunction "TCK_B2") (pintype "bidirectional"))
    )
    (net (code "215") (name "unconnected-(U$1-TMS-PadA2)") (class "Default")
      (node (ref "U$1") (pin "A2") (pinfunction "TMS_A2") (pintype "bidirectional"))
    )
    (net (code "216") (name "unconnected-(U$1-~{GRST}-PadB5)") (class "Default")
      (node (ref "U$1") (pin "B5") (pinfunction "~{GRST}_B5") (pintype "bidirectional"))
    )
  )
)
